# Word_Clock.net
KiCad netlist of a schematic drawn in EAGLE
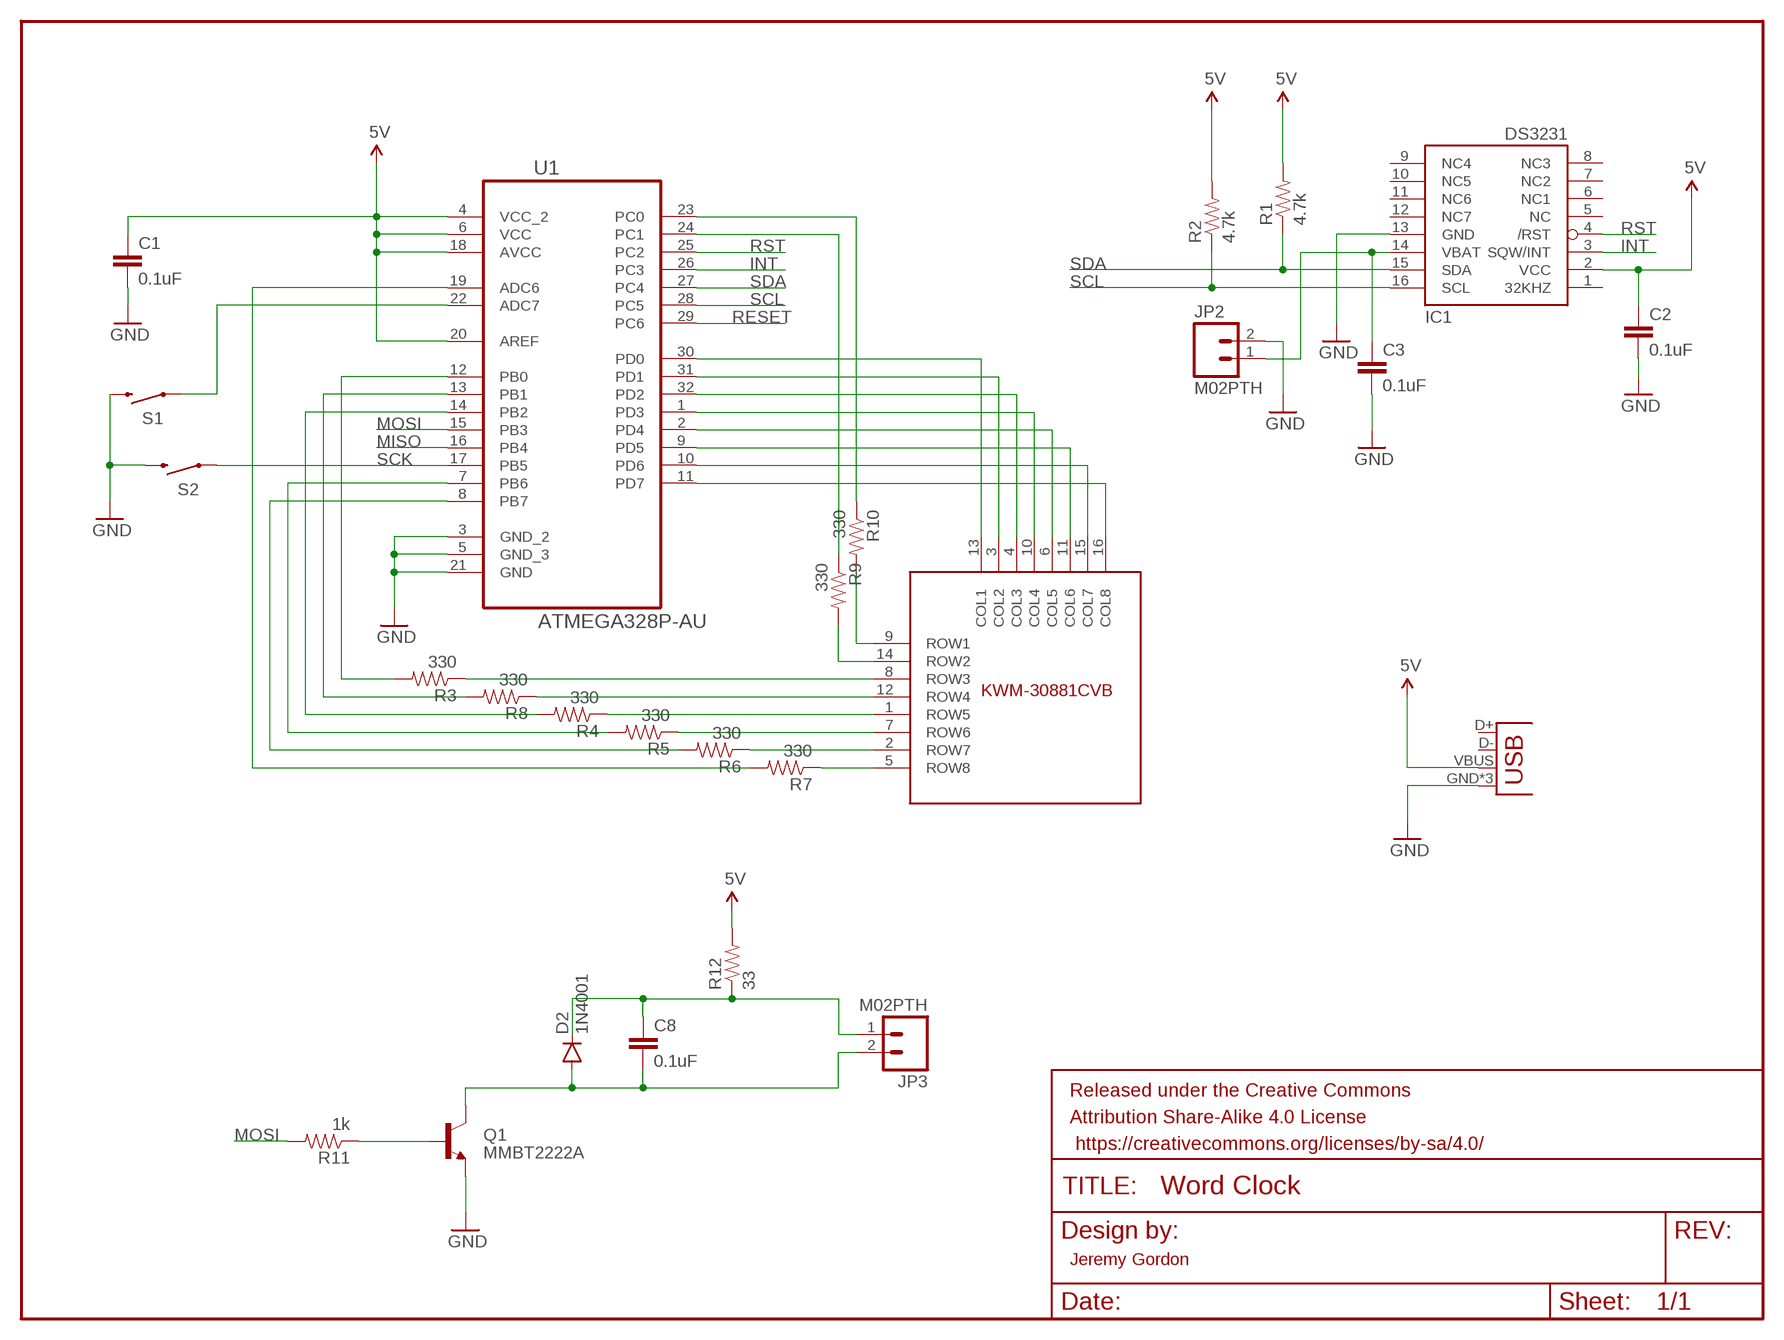
[diagram p0: schematic, sheet 1]

(export (version "E")
  (design (tool "Eeschema 10.0.6"))
  (components
    (comp (ref "C1")
      (value "0.1uF")
      (footprint "eagle-import:0805")
      (libsource (lib "eagle-import") (part "CAP0805"))
    )
    (comp (ref "C2")
      (value "0.1uF")
      (footprint "eagle-import:0805")
      (libsource (lib "eagle-import") (part "CAP0805"))
    )
    (comp (ref "C3")
      (value "0.1uF")
      (footprint "eagle-import:0805")
      (libsource (lib "eagle-import") (part "CAP0805"))
    )
    (comp (ref "C8")
      (value "0.1uF")
      (footprint "eagle-import:0805")
      (libsource (lib "eagle-import") (part "CAP0805"))
    )
    (comp (ref "D1")
      (value "KWM-30881CVB")
      (footprint "eagle-import:KWM-30881CVB")
      (libsource (lib "eagle-import") (part "KWM-30881CVB"))
    )
    (comp (ref "D2")
      (value "1N4001")
      (footprint "eagle-import:SOD-323")
      (libsource (lib "eagle-import") (part "DIODESOD"))
    )
    (comp (ref "FRAME1")
      (value "FRAME-LETTER")
      (footprint "eagle-import:CREATIVE_COMMONS")
      (libsource (lib "eagle-import") (part "FRAME-LETTER"))
    )
    (comp (ref "IC1")
      (value "DS3231/SO")
      (footprint "eagle-import:SO16W")
      (libsource (lib "eagle-import") (part "DS3231/SO"))
    )
    (comp (ref "JP1")
      (value "USB-MICROB")
      (footprint "eagle-import:USB-MICROB")
      (libsource (lib "eagle-import") (part "USB-MICROB"))
    )
    (comp (ref "JP2")
      (value "M02PTH")
      (footprint "eagle-import:1X02")
      (libsource (lib "eagle-import") (part "M02PTH"))
    )
    (comp (ref "JP3")
      (value "M02PTH")
      (footprint "eagle-import:1X02")
      (libsource (lib "eagle-import") (part "M02PTH"))
    )
    (comp (ref "Q1")
      (value "MMBT2222A")
      (footprint "eagle-import:SOT23-3")
      (libsource (lib "eagle-import") (part "TRANSISTOR_NPNMMBT2222A"))
    )
    (comp (ref "R1")
      (value "4.7k")
      (footprint "eagle-import:0805")
      (libsource (lib "eagle-import") (part "RESISTOR0805-RES"))
    )
    (comp (ref "R2")
      (value "4.7k")
      (footprint "eagle-import:0805")
      (libsource (lib "eagle-import") (part "RESISTOR0805-RES"))
    )
    (comp (ref "R3")
      (value "330")
      (footprint "eagle-import:0805")
      (libsource (lib "eagle-import") (part "RESISTOR0805-RES"))
    )
    (comp (ref "R4")
      (value "330")
      (footprint "eagle-import:0805")
      (libsource (lib "eagle-import") (part "RESISTOR0805-RES"))
    )
    (comp (ref "R5")
      (value "330")
      (footprint "eagle-import:0805")
      (libsource (lib "eagle-import") (part "RESISTOR0805-RES"))
    )
    (comp (ref "R6")
      (value "330")
      (footprint "eagle-import:0805")
      (libsource (lib "eagle-import") (part "RESISTOR0805-RES"))
    )
    (comp (ref "R7")
      (value "330")
      (footprint "eagle-import:0805")
      (libsource (lib "eagle-import") (part "RESISTOR0805-RES"))
    )
    (comp (ref "R8")
      (value "330")
      (footprint "eagle-import:0805")
      (libsource (lib "eagle-import") (part "RESISTOR0805-RES"))
    )
    (comp (ref "R9")
      (value "330")
      (footprint "eagle-import:0805")
      (libsource (lib "eagle-import") (part "RESISTOR0805-RES"))
    )
    (comp (ref "R10")
      (value "330")
      (footprint "eagle-import:0805")
      (libsource (lib "eagle-import") (part "RESISTOR0805-RES"))
    )
    (comp (ref "R11")
      (value "1k")
      (footprint "eagle-import:0805")
      (libsource (lib "eagle-import") (part "RESISTOR0805-RES"))
    )
    (comp (ref "R12")
      (value "33")
      (footprint "eagle-import:0805")
      (libsource (lib "eagle-import") (part "RESISTOR0805-RES"))
    )
    (comp (ref "S1")
      (value "SWITCH-MOMENTARY-2SMD-1101NE")
      (footprint "eagle-import:TACTILE-SWITCH-1101NE")
      (libsource (lib "eagle-import") (part "SWITCH-MOMENTARY-2SMD-1101NE"))
    )
    (comp (ref "S2")
      (value "SWITCH-MOMENTARY-2SMD-1101NE")
      (footprint "eagle-import:TACTILE-SWITCH-1101NE")
      (libsource (lib "eagle-import") (part "SWITCH-MOMENTARY-2SMD-1101NE"))
    )
    (comp (ref "U1")
      (value "ATMEGA328P-AU")
      (footprint "eagle-import:QFP80P900X900X120-32N")
      (libsource (lib "eagle-import") (part "ATMEGA328P-AU"))
    )
  )
  (nets
    (net (code "1") (name "/INT") (class "Default")
      (node (ref "IC1") (pin "3") (pinfunction "SQW/INT_3") (pintype "output"))
      (node (ref "U1") (pin "26") (pinfunction "PC3_26") (pintype "bidirectional"))
    )
    (net (code "2") (name "/MISO") (class "Default")
      (node (ref "U1") (pin "16") (pinfunction "PB4_16") (pintype "bidirectional"))
    )
    (net (code "3") (name "/MOSI") (class "Default")
      (node (ref "R11") (pin "2") (pinfunction "2_2") (pintype "passive"))
      (node (ref "U1") (pin "15") (pinfunction "PB3_15") (pintype "bidirectional"))
    )
    (net (code "4") (name "/RESET") (class "Default")
      (node (ref "U1") (pin "29") (pinfunction "PC6_29") (pintype "bidirectional"))
    )
    (net (code "5") (name "/RST") (class "Default")
      (node (ref "IC1") (pin "4") (pinfunction "/RST_4") (pintype "passive"))
      (node (ref "U1") (pin "25") (pinfunction "PC2_25") (pintype "bidirectional"))
    )
    (net (code "6") (name "/SCK") (class "Default")
      (node (ref "S2") (pin "1") (pinfunction "1_1") (pintype "passive"))
      (node (ref "U1") (pin "17") (pinfunction "PB5_17") (pintype "bidirectional"))
    )
    (net (code "7") (name "/SCL") (class "Default")
      (node (ref "IC1") (pin "16") (pinfunction "SCL_16") (pintype "bidirectional"))
      (node (ref "R2") (pin "1") (pinfunction "1_1") (pintype "passive"))
      (node (ref "U1") (pin "28") (pinfunction "PC5_28") (pintype "bidirectional"))
    )
    (net (code "8") (name "/SDA") (class "Default")
      (node (ref "IC1") (pin "15") (pinfunction "SDA_15") (pintype "bidirectional"))
      (node (ref "R1") (pin "1") (pinfunction "1_1") (pintype "passive"))
      (node (ref "U1") (pin "27") (pinfunction "PC4_27") (pintype "bidirectional"))
    )
    (net (code "9") (name "5V") (class "Default")
      (node (ref "C1") (pin "1") (pinfunction "1_1") (pintype "passive"))
      (node (ref "C2") (pin "1") (pinfunction "1_1") (pintype "passive"))
      (node (ref "IC1") (pin "2") (pinfunction "VCC_2") (pintype "power_in"))
      (node (ref "JP1") (pin "VBUS") (pinfunction "VBUS_VBUS") (pintype "bidirectional"))
      (node (ref "R1") (pin "2") (pinfunction "2_2") (pintype "passive"))
      (node (ref "R12") (pin "2") (pinfunction "2_2") (pintype "passive"))
      (node (ref "R2") (pin "2") (pinfunction "2_2") (pintype "passive"))
      (node (ref "U1") (pin "18") (pinfunction "AVCC_18") (pintype "power_in"))
      (node (ref "U1") (pin "20") (pinfunction "AREF_20") (pintype "input"))
      (node (ref "U1") (pin "4") (pinfunction "VCC_2_4") (pintype "power_in"))
      (node (ref "U1") (pin "6") (pinfunction "VCC_6") (pintype "power_in"))
    )
    (net (code "10") (name "GND") (class "Default")
      (node (ref "C1") (pin "2") (pinfunction "2_2") (pintype "passive"))
      (node (ref "C2") (pin "2") (pinfunction "2_2") (pintype "passive"))
      (node (ref "C3") (pin "2") (pinfunction "2_2") (pintype "passive"))
      (node (ref "IC1") (pin "13") (pinfunction "GND_13") (pintype "power_in"))
      (node (ref "JP1") (pin "GND") (pinfunction "GND_GND") (pintype "bidirectional"))
      (node (ref "JP1") (pin "MT1") (pinfunction "GND_MT1") (pintype "bidirectional"))
      (node (ref "JP1") (pin "MT2") (pinfunction "GND_MT2") (pintype "bidirectional"))
      (node (ref "JP2") (pin "2") (pinfunction "2_2") (pintype "passive"))
      (node (ref "Q1") (pin "2") (pinfunction "E_2") (pintype "passive"))
      (node (ref "S1") (pin "2") (pinfunction "2_2") (pintype "passive"))
      (node (ref "S2") (pin "2") (pinfunction "2_2") (pintype "passive"))
      (node (ref "U1") (pin "21") (pinfunction "GND_21") (pintype "passive"))
      (node (ref "U1") (pin "3") (pinfunction "GND_2_3") (pintype "passive"))
      (node (ref "U1") (pin "5") (pinfunction "GND_3_5") (pintype "passive"))
    )
    (net (code "11") (name "Net-(C8-Pad1)") (class "Default")
      (node (ref "C8") (pin "1") (pinfunction "1_1") (pintype "passive"))
      (node (ref "D2") (pin "C") (pinfunction "C_C") (pintype "passive"))
      (node (ref "JP3") (pin "1") (pinfunction "1_1") (pintype "passive"))
      (node (ref "R12") (pin "1") (pinfunction "1_1") (pintype "passive"))
    )
    (net (code "12") (name "Net-(D1-COL1)") (class "Default")
      (node (ref "D1") (pin "13") (pinfunction "COL1_13") (pintype "bidirectional"))
      (node (ref "U1") (pin "30") (pinfunction "PD0_30") (pintype "bidirectional"))
    )
    (net (code "13") (name "Net-(D1-COL2)") (class "Default")
      (node (ref "D1") (pin "3") (pinfunction "COL2_3") (pintype "bidirectional"))
      (node (ref "U1") (pin "31") (pinfunction "PD1_31") (pintype "bidirectional"))
    )
    (net (code "14") (name "Net-(D1-COL3)") (class "Default")
      (node (ref "D1") (pin "4") (pinfunction "COL3_4") (pintype "bidirectional"))
      (node (ref "U1") (pin "32") (pinfunction "PD2_32") (pintype "bidirectional"))
    )
    (net (code "15") (name "Net-(D1-COL4)") (class "Default")
      (node (ref "D1") (pin "10") (pinfunction "COL4_10") (pintype "bidirectional"))
      (node (ref "U1") (pin "1") (pinfunction "PD3_1") (pintype "bidirectional"))
    )
    (net (code "16") (name "Net-(D1-COL5)") (class "Default")
      (node (ref "D1") (pin "6") (pinfunction "COL5_6") (pintype "bidirectional"))
      (node (ref "U1") (pin "2") (pinfunction "PD4_2") (pintype "bidirectional"))
    )
    (net (code "17") (name "Net-(D1-COL6)") (class "Default")
      (node (ref "D1") (pin "11") (pinfunction "COL6_11") (pintype "bidirectional"))
      (node (ref "U1") (pin "9") (pinfunction "PD5_9") (pintype "bidirectional"))
    )
    (net (code "18") (name "Net-(D1-COL7)") (class "Default")
      (node (ref "D1") (pin "15") (pinfunction "COL7_15") (pintype "bidirectional"))
      (node (ref "U1") (pin "10") (pinfunction "PD6_10") (pintype "bidirectional"))
    )
    (net (code "19") (name "Net-(D1-COL8)") (class "Default")
      (node (ref "D1") (pin "16") (pinfunction "COL8_16") (pintype "bidirectional"))
      (node (ref "U1") (pin "11") (pinfunction "PD7_11") (pintype "bidirectional"))
    )
    (net (code "20") (name "Net-(D1-ROW1)") (class "Default")
      (node (ref "D1") (pin "9") (pinfunction "ROW1_9") (pintype "bidirectional"))
      (node (ref "R10") (pin "2") (pinfunction "2_2") (pintype "passive"))
    )
    (net (code "21") (name "Net-(D1-ROW2)") (class "Default")
      (node (ref "D1") (pin "14") (pinfunction "ROW2_14") (pintype "bidirectional"))
      (node (ref "R9") (pin "2") (pinfunction "2_2") (pintype "passive"))
    )
    (net (code "22") (name "Net-(D1-ROW3)") (class "Default")
      (node (ref "D1") (pin "8") (pinfunction "ROW3_8") (pintype "bidirectional"))
      (node (ref "R3") (pin "1") (pinfunction "1_1") (pintype "passive"))
    )
    (net (code "23") (name "Net-(D1-ROW4)") (class "Default")
      (node (ref "D1") (pin "12") (pinfunction "ROW4_12") (pintype "bidirectional"))
      (node (ref "R8") (pin "1") (pinfunction "1_1") (pintype "passive"))
    )
    (net (code "24") (name "Net-(D1-ROW5)") (class "Default")
      (node (ref "D1") (pin "1") (pinfunction "ROW5_1") (pintype "bidirectional"))
      (node (ref "R4") (pin "1") (pinfunction "1_1") (pintype "passive"))
    )
    (net (code "25") (name "Net-(D1-ROW6)") (class "Default")
      (node (ref "D1") (pin "7") (pinfunction "ROW6_7") (pintype "bidirectional"))
      (node (ref "R5") (pin "1") (pinfunction "1_1") (pintype "passive"))
    )
    (net (code "26") (name "Net-(D1-ROW7)") (class "Default")
      (node (ref "D1") (pin "2") (pinfunction "ROW7_2") (pintype "bidirectional"))
      (node (ref "R6") (pin "1") (pinfunction "1_1") (pintype "passive"))
    )
    (net (code "27") (name "Net-(D1-ROW8)") (class "Default")
      (node (ref "D1") (pin "5") (pinfunction "ROW8_5") (pintype "bidirectional"))
      (node (ref "R7") (pin "1") (pinfunction "1_1") (pintype "passive"))
    )
    (net (code "28") (name "Net-(IC1-VBAT)") (class "Default")
      (node (ref "C3") (pin "1") (pinfunction "1_1") (pintype "passive"))
      (node (ref "IC1") (pin "14") (pinfunction "VBAT_14") (pintype "power_in"))
      (node (ref "JP2") (pin "1") (pinfunction "1_1") (pintype "passive"))
    )
    (net (code "29") (name "Net-(Q1-B)") (class "Default")
      (node (ref "Q1") (pin "1") (pinfunction "B_1") (pintype "passive"))
      (node (ref "R11") (pin "1") (pinfunction "1_1") (pintype "passive"))
    )
    (net (code "30") (name "Net-(Q1-C)") (class "Default")
      (node (ref "C8") (pin "2") (pinfunction "2_2") (pintype "passive"))
      (node (ref "D2") (pin "A") (pinfunction "A_A") (pintype "passive"))
      (node (ref "JP3") (pin "2") (pinfunction "2_2") (pintype "passive"))
      (node (ref "Q1") (pin "3") (pinfunction "C_3") (pintype "passive"))
    )
    (net (code "31") (name "Net-(U1-ADC6)") (class "Default")
      (node (ref "R7") (pin "2") (pinfunction "2_2") (pintype "passive"))
      (node (ref "U1") (pin "19") (pinfunction "ADC6_19") (pintype "input"))
    )
    (net (code "32") (name "Net-(U1-ADC7)") (class "Default")
      (node (ref "S1") (pin "1") (pinfunction "1_1") (pintype "passive"))
      (node (ref "U1") (pin "22") (pinfunction "ADC7_22") (pintype "input"))
    )
    (net (code "33") (name "Net-(U1-PB0)") (class "Default")
      (node (ref "R3") (pin "2") (pinfunction "2_2") (pintype "passive"))
      (node (ref "U1") (pin "12") (pinfunction "PB0_12") (pintype "bidirectional"))
    )
    (net (code "34") (name "Net-(U1-PB1)") (class "Default")
      (node (ref "R8") (pin "2") (pinfunction "2_2") (pintype "passive"))
      (node (ref "U1") (pin "13") (pinfunction "PB1_13") (pintype "bidirectional"))
    )
    (net (code "35") (name "Net-(U1-PB2)") (class "Default")
      (node (ref "R4") (pin "2") (pinfunction "2_2") (pintype "passive"))
      (node (ref "U1") (pin "14") (pinfunction "PB2_14") (pintype "bidirectional"))
    )
    (net (code "36") (name "Net-(U1-PB6)") (class "Default")
      (node (ref "R5") (pin "2") (pinfunction "2_2") (pintype "passive"))
      (node (ref "U1") (pin "7") (pinfunction "PB6_7") (pintype "bidirectional"))
    )
    (net (code "37") (name "Net-(U1-PB7)") (class "Default")
      (node (ref "R6") (pin "2") (pinfunction "2_2") (pintype "passive"))
      (node (ref "U1") (pin "8") (pinfunction "PB7_8") (pintype "bidirectional"))
    )
    (net (code "38") (name "Net-(U1-PC0)") (class "Default")
      (node (ref "R10") (pin "1") (pinfunction "1_1") (pintype "passive"))
      (node (ref "U1") (pin "23") (pinfunction "PC0_23") (pintype "bidirectional"))
    )
    (net (code "39") (name "Net-(U1-PC1)") (class "Default")
      (node (ref "R9") (pin "1") (pinfunction "1_1") (pintype "passive"))
      (node (ref "U1") (pin "24") (pinfunction "PC1_24") (pintype "bidirectional"))
    )
    (net (code "40") (name "unconnected-(IC1-32KHZ-Pad1)") (class "Default")
      (node (ref "IC1") (pin "1") (pinfunction "32KHZ_1") (pintype "output"))
    )
    (net (code "41") (name "unconnected-(IC1-NC-Pad5)") (class "Default")
      (node (ref "IC1") (pin "5") (pinfunction "NC_5") (pintype "no_connect"))
    )
    (net (code "42") (name "unconnected-(IC1-NC1-Pad6)") (class "Default")
      (node (ref "IC1") (pin "6") (pinfunction "NC1_6") (pintype "no_connect"))
    )
    (net (code "43") (name "unconnected-(IC1-NC2-Pad7)") (class "Default")
      (node (ref "IC1") (pin "7") (pinfunction "NC2_7") (pintype "no_connect"))
    )
    (net (code "44") (name "unconnected-(IC1-NC3-Pad8)") (class "Default")
      (node (ref "IC1") (pin "8") (pinfunction "NC3_8") (pintype "no_connect"))
    )
    (net (code "45") (name "unconnected-(IC1-NC4-Pad9)") (class "Default")
      (node (ref "IC1") (pin "9") (pinfunction "NC4_9") (pintype "no_connect"))
    )
    (net (code "46") (name "unconnected-(IC1-NC5-Pad10)") (class "Default")
      (node (ref "IC1") (pin "10") (pinfunction "NC5_10") (pintype "no_connect"))
    )
    (net (code "47") (name "unconnected-(IC1-NC6-Pad11)") (class "Default")
      (node (ref "IC1") (pin "11") (pinfunction "NC6_11") (pintype "no_connect"))
    )
    (net (code "48") (name "unconnected-(IC1-NC7-Pad12)") (class "Default")
      (node (ref "IC1") (pin "12") (pinfunction "NC7_12") (pintype "no_connect"))
    )
    (net (code "49") (name "unconnected-(JP1-PadD+)") (class "Default")
      (node (ref "JP1") (pin "D+") (pinfunction "D+_D+") (pintype "bidirectional"))
    )
    (net (code "50") (name "unconnected-(JP1-PadD-)") (class "Default")
      (node (ref "JP1") (pin "D-") (pinfunction "D-_D-") (pintype "bidirectional"))
    )
  )
)
